# RS485Click.net
KiCad netlist of a schematic drawn in Altium Designer
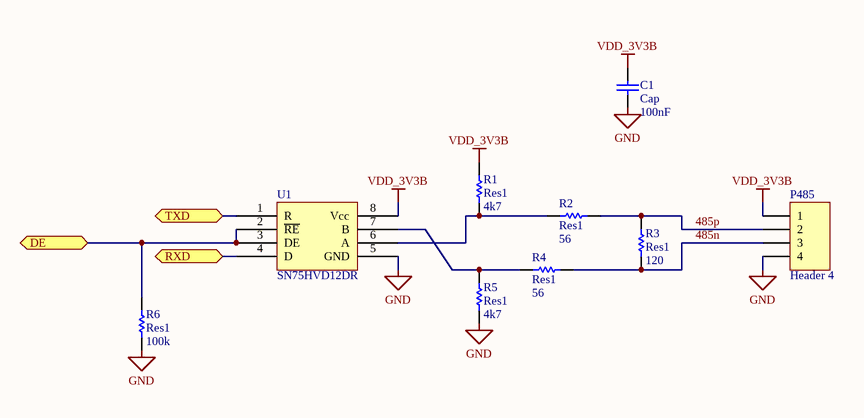
[diagram p0: RS485Click.SchDoc]

(export (version "E")
  (design (tool "Eeschema 10.0.6"))
  (components
    (comp (ref "C1")
      (value "Cap")
      (footprint "RAD-0.3")
      (description "Capacitor")
      (fields (field (name "ALTIUM_VALUE") "100nF") (field (name "PUBLISHER") "Altium Limited"))
      (libsource (lib "Miscellaneous Devices") (part "Cap"))
    )
    (comp (ref "P485")
      (value "Header 4")
      (footprint "HDR1X4")
      (description "Header, 4-Pin")
      (fields (field (name "PUBLISHER") "Altium Limited"))
      (libsource (lib "Miscellaneous Connectors") (part "Header 4"))
    )
    (comp (ref "R1")
      (value "Res1")
      (footprint "AXIAL-0.3")
      (description "Resistor")
      (fields (field (name "ALTIUM_VALUE") "4k7") (field (name "PUBLISHER") "Altium Limited"))
      (libsource (lib "Miscellaneous Devices") (part "Res1"))
    )
    (comp (ref "R2")
      (value "Res1")
      (footprint "AXIAL-0.3")
      (description "Resistor")
      (fields (field (name "ALTIUM_VALUE") "56") (field (name "PUBLISHER") "Altium Limited"))
      (libsource (lib "Miscellaneous Devices") (part "Res1"))
    )
    (comp (ref "R3")
      (value "Res1")
      (footprint "AXIAL-0.3")
      (description "Resistor")
      (fields (field (name "ALTIUM_VALUE") "120") (field (name "PUBLISHER") "Altium Limited"))
      (libsource (lib "Miscellaneous Devices") (part "Res1"))
    )
    (comp (ref "R4")
      (value "Res1")
      (footprint "AXIAL-0.3")
      (description "Resistor")
      (fields (field (name "ALTIUM_VALUE") "56") (field (name "PUBLISHER") "Altium Limited"))
      (libsource (lib "Miscellaneous Devices") (part "Res1"))
    )
    (comp (ref "R5")
      (value "Res1")
      (footprint "AXIAL-0.3")
      (description "Resistor")
      (fields (field (name "ALTIUM_VALUE") "4k7") (field (name "PUBLISHER") "Altium Limited"))
      (libsource (lib "Miscellaneous Devices") (part "Res1"))
    )
    (comp (ref "R6")
      (value "Res1")
      (footprint "AXIAL-0.3")
      (description "Resistor")
      (fields (field (name "ALTIUM_VALUE") "100k") (field (name "PUBLISHER") "Altium Limited"))
      (libsource (lib "Miscellaneous Devices") (part "Res1"))
    )
    (comp (ref "U1")
      (value "SN75HVD12DR")
      (footprint "SOIC127P599X175-8N")
      (fields (field (name "VENDOR PART NUMBER") "296-26658-1-ND"))
      (libsource (lib "BeagleCape") (part "SN75HVD12DR"))
    )
  )
  (nets
    (net (code "1") (name "/485n") (class "Default")
      (node (ref "P485") (pin "3") (pinfunction "3_3") (pintype "passive"))
      (node (ref "R3") (pin "1") (pinfunction "1_1") (pintype "passive"))
      (node (ref "R4") (pin "1") (pinfunction "1_1") (pintype "passive"))
    )
    (net (code "2") (name "/485p") (class "Default")
      (node (ref "P485") (pin "2") (pinfunction "2_2") (pintype "passive"))
      (node (ref "R2") (pin "1") (pinfunction "1_1") (pintype "passive"))
      (node (ref "R3") (pin "2") (pinfunction "2_2") (pintype "passive"))
    )
    (net (code "3") (name "/DE") (class "Default")
      (node (ref "R6") (pin "1") (pinfunction "1_1") (pintype "passive"))
      (node (ref "U1") (pin "2") (pinfunction "~{RE}_2") (pintype "passive"))
      (node (ref "U1") (pin "3") (pinfunction "DE_3") (pintype "passive"))
    )
    (net (code "4") (name "/RXD") (class "Default")
      (node (ref "U1") (pin "4") (pinfunction "D_4") (pintype "passive"))
    )
    (net (code "5") (name "/TXD") (class "Default")
      (node (ref "U1") (pin "1") (pinfunction "R_1") (pintype "passive"))
    )
    (net (code "6") (name "GND") (class "Default")
      (node (ref "C1") (pin "1") (pinfunction "1_1") (pintype "passive"))
      (node (ref "P485") (pin "4") (pinfunction "4_4") (pintype "passive"))
      (node (ref "R5") (pin "2") (pinfunction "2_2") (pintype "passive"))
      (node (ref "R6") (pin "2") (pinfunction "2_2") (pintype "passive"))
      (node (ref "U1") (pin "5") (pinfunction "GND_5") (pintype "passive"))
    )
    (net (code "7") (name "Net-(U1-A)") (class "Default")
      (node (ref "R1") (pin "2") (pinfunction "2_2") (pintype "passive"))
      (node (ref "R2") (pin "2") (pinfunction "2_2") (pintype "passive"))
      (node (ref "U1") (pin "6") (pinfunction "A_6") (pintype "passive"))
    )
    (net (code "8") (name "Net-(U1-B)") (class "Default")
      (node (ref "R4") (pin "2") (pinfunction "2_2") (pintype "passive"))
      (node (ref "R5") (pin "1") (pinfunction "1_1") (pintype "passive"))
      (node (ref "U1") (pin "7") (pinfunction "B_7") (pintype "passive"))
    )
    (net (code "9") (name "VDD_3V3B") (class "Default")
      (node (ref "C1") (pin "2") (pinfunction "2_2") (pintype "passive"))
      (node (ref "P485") (pin "1") (pinfunction "1_1") (pintype "passive"))
      (node (ref "R1") (pin "1") (pinfunction "1_1") (pintype "passive"))
      (node (ref "U1") (pin "8") (pinfunction "Vcc_8") (pintype "passive"))
    )
  )
)
